# power.net
KiCad netlist of a schematic drawn in Altium Designer
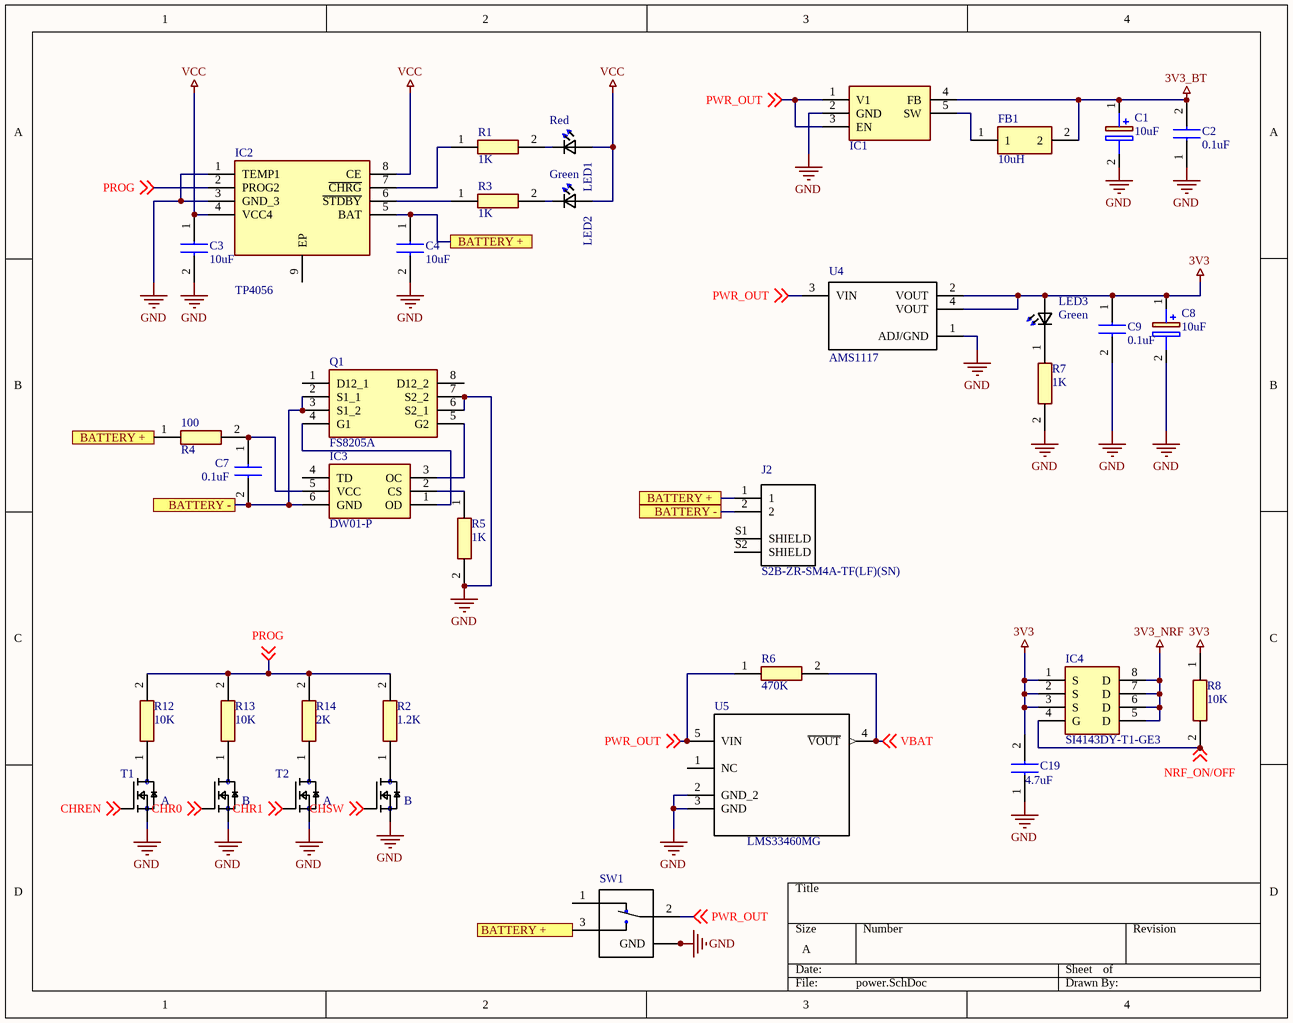
[diagram p0: power.SchDoc]

(export (version "E")
  (design (tool "Eeschema 10.0.6"))
  (components
    (comp (ref "C1")
      (value "10uF")
      (footprint "CAPPM3216X180N")
      (description "Capacitor Polarised")
      (fields (field (name "Comment") "tantalum capacitor 1206"))
      (libsource (lib "Radio Lib") (part "tantalum capacitor 1206"))
    )
    (comp (ref "C2")
      (value "0.1uF")
      (footprint "*CAPC1608X95N")
      (description "Capacitor")
      (fields (field (name "Comment") "capacitor 0603"))
      (libsource (lib "Radio Lib") (part "capacitor 0603"))
    )
    (comp (ref "C3")
      (value "10uF")
      (footprint "CAPC2012X94N")
      (description "Capacitor")
      (fields
        (field (name "MANUFACTURER_PART_NUMBER") "08055A101JAT2A")
        (field (name "MOUSER PART NUMBER") "581-08055A101J")
      )
      (libsource (lib "Radio Lib") (part "08055A101JAT2A"))
    )
    (comp (ref "C4")
      (value "10uF")
      (footprint "CAPC2012X94N")
      (description "Capacitor")
      (fields
        (field (name "MANUFACTURER_PART_NUMBER") "08055A101JAT2A")
        (field (name "MOUSER PART NUMBER") "581-08055A101J")
      )
      (libsource (lib "Radio Lib") (part "08055A101JAT2A"))
    )
    (comp (ref "C7")
      (value "0.1uF")
      (footprint "CAPC2012X94N")
      (description "Capacitor")
      (fields
        (field (name "MANUFACTURER_PART_NUMBER") "08055A101JAT2A")
        (field (name "MOUSER PART NUMBER") "581-08055A101J")
      )
      (libsource (lib "Radio Lib") (part "08055A101JAT2A"))
    )
    (comp (ref "C8")
      (value "10uF")
      (footprint "CAPPM3216X180N")
      (description "Capacitor Polarised")
      (fields (field (name "Comment") "tantalum capacitor 1206"))
      (libsource (lib "Radio Lib") (part "tantalum capacitor 1206"))
    )
    (comp (ref "C9")
      (value "0.1uF")
      (footprint "*CAPC1608X95N")
      (description "Capacitor")
      (fields (field (name "Comment") "capacitor 0603"))
      (libsource (lib "Radio Lib") (part "capacitor 0603"))
    )
    (comp (ref "C19")
      (value "4.7uF")
      (footprint "CAPC2012X94N")
      (description "Capacitor")
      (fields
        (field (name "MANUFACTURER_PART_NUMBER") "08055A101JAT2A")
        (field (name "MOUSER PART NUMBER") "581-08055A101J")
      )
      (libsource (lib "micromouse library") (part "08055A101JAT2A"))
    )
    (comp (ref "FB1")
      (value "10uH")
      (footprint "BEADC1608X95N")
      (description "Ferrite Bead")
      (fields (field (name "Comment") "inductor 0603"))
      (libsource (lib "Radio Lib") (part "inductor 0603"))
    )
    (comp (ref "IC1")
      (value "TPS62203")
      (footprint "SOT95P280X145-5N")
      (description "Integrated Circuit")
      (libsource (lib "Radio Lib") (part "TPS62203"))
    )
    (comp (ref "IC2")
      (value "TP4056")
      (footprint "SOIC127P600X175-9N")
      (description "Integrated Circuit")
      (libsource (lib "Radio Lib") (part "TP4056"))
    )
    (comp (ref "IC3")
      (value "DW01-P")
      (footprint "micromouse pcb library:SOT95P280X135-6N")
      (description "Integrated Circuit")
      (libsource (lib "Radio Lib") (part "DW01-P"))
    )
    (comp (ref "IC4")
      (value "SI4143DY-T1-GE3")
      (footprint "SI4143DY-T1-GE3")
      (description "Integrated Circuit")
      (libsource (lib "Radio Lib") (part "SI4143DY-T1-GE3"))
    )
    (comp (ref "J2")
      (value "S2B-ZR-SM4A-TF(LF)(SN)")
      (footprint "*JST_S2B-ZR-SM4A-TF(LF)(SN)_S2B-ZR-SM4A-TF(LF)(SN)(Primary)")
      (description "Connector Header Surface Mount, Right Angle 2 position 0.059 _1.50mm_")
      (fields (field (name "MF") "JST Sales") (field (name "MP") "S2B-ZR-SM4A-TF_LF__SN_"))
      (libsource (lib "Radio Lib") (part "S2B-ZR-SM4A-TF(LF)(SN)"))
    )
    (comp (ref "LED1")
      (value "Red")
      (footprint "*0603")
      (description "LED Indication - Discrete 3.4V 0603 _1608 Metric_")
      (fields (field (name "MP") "HSMR-C191") (field (name "MF") "Broadcom Limited"))
      (libsource (lib "Radio Lib") (part "HSMR-C191"))
    )
    (comp (ref "LED2")
      (value "Green")
      (footprint "*0603")
      (description "LED Indication - Discrete 3.4V 0603 _1608 Metric_")
      (fields (field (name "MP") "HSMR-C191") (field (name "MF") "Broadcom Limited"))
      (libsource (lib "Radio Lib") (part "HSMR-C191"))
    )
    (comp (ref "LED3")
      (value "Green")
      (footprint "*0603")
      (description "LED Indication - Discrete 3.4V 0603 _1608 Metric_")
      (fields (field (name "MP") "HSMR-C191") (field (name "MF") "Broadcom Limited"))
      (libsource (lib "Radio Lib") (part "HSMR-C191"))
    )
    (comp (ref "Q1")
      (value "FS8205A")
      (footprint "SOP65P640X120-8N")
      (description "Transistor")
      (libsource (lib "Radio Lib") (part "FS8205A"))
    )
    (comp (ref "R1")
      (value "1K")
      (footprint "RESC1608X55N")
      (description "Resistor")
      (fields (field (name "Comment") "resistor"))
      (libsource (lib "") (part "resistor_2"))
    )
    (comp (ref "R2")
      (value "1.2K")
      (footprint "RESC1608X55N")
      (description "Resistor")
      (fields (field (name "Comment") "resistor"))
      (libsource (lib "") (part "resistor_1"))
    )
    (comp (ref "R3")
      (value "1K")
      (footprint "RESC1608X55N")
      (description "Resistor")
      (fields (field (name "Comment") "resistor"))
      (libsource (lib "") (part "resistor_2"))
    )
    (comp (ref "R4")
      (value "100")
      (footprint "RESC2012X65N")
      (description "Resistor")
      (fields
        (field (name "MANUFACTURER_PART_NUMBER") "CPF0805B100KE")
        (field (name "MOUSER PART NUMBER") "279-CPF0805B100KE")
      )
      (libsource (lib "") (part "CPF0805_1"))
    )
    (comp (ref "R5")
      (value "1K")
      (footprint "RESC2012X65N")
      (description "Resistor")
      (fields
        (field (name "MANUFACTURER_PART_NUMBER") "CPF0805B100KE")
        (field (name "MOUSER PART NUMBER") "279-CPF0805B100KE")
      )
      (libsource (lib "Radio Lib") (part "CPF0805"))
    )
    (comp (ref "R6")
      (value "470K")
      (footprint "RESC1608X55N")
      (description "Resistor")
      (fields (field (name "Comment") "resistor"))
      (libsource (lib "") (part "resistor_2"))
    )
    (comp (ref "R7")
      (value "1K")
      (footprint "RESC1608X55N")
      (description "Resistor")
      (fields (field (name "Comment") "resistor"))
      (libsource (lib "Radio Lib") (part "resistor"))
    )
    (comp (ref "R8")
      (value "10K")
      (footprint "RESC2012X65N")
      (description "Resistor")
      (fields
        (field (name "MANUFACTURER_PART_NUMBER") "CPF0805B100KE")
        (field (name "MOUSER PART NUMBER") "279-CPF0805B100KE")
      )
      (libsource (lib "Radio Lib") (part "CPF0805"))
    )
    (comp (ref "R12")
      (value "10K")
      (footprint "RESC1608X55N")
      (description "Resistor")
      (fields (field (name "Comment") "resistor"))
      (libsource (lib "") (part "resistor_1"))
    )
    (comp (ref "R13")
      (value "10K")
      (footprint "RESC1608X55N")
      (description "Resistor")
      (fields (field (name "Comment") "resistor"))
      (libsource (lib "") (part "resistor_1"))
    )
    (comp (ref "R14")
      (value "2K")
      (footprint "RESC1608X55N")
      (description "Resistor")
      (fields (field (name "Comment") "resistor"))
      (libsource (lib "") (part "resistor_1"))
    )
    (comp (ref "SW1")
      (value "1437575-1")
      (footprint "*SW_MLL1200S_MLL1200S(Primary)")
      (description "Slide Switch SPDT Surface Mount, Right Angle")
      (fields (field (name "MP") "MLL1200S") (field (name "MF") "TE Connectivity"))
      (libsource (lib "Radio Lib") (part "MLL1200S"))
    )
    (comp (ref "T1")
      (value "PMGD780SN")
      (footprint "*SOP65P210X110-6N")
      (description "Mosfet Array 2 N-Channel _Dual_ 20V 1.2A 390mW Surface Mount 6-TSSOP")
      (fields (field (name "MF") "NXP Semiconductors"))
      (libsource (lib "Radio Lib") (part "PMGD780SN"))
    )
    (comp (ref "T2")
      (value "PMGD780SN")
      (footprint "*SOP65P210X110-6N")
      (description "Mosfet Array 2 N-Channel _Dual_ 20V 1.2A 390mW Surface Mount 6-TSSOP")
      (fields (field (name "MF") "NXP Semiconductors"))
      (libsource (lib "Radio Lib") (part "PMGD780SN"))
    )
    (comp (ref "U4")
      (value "AMS1117")
      (footprint "*SOT229P700X180-4N")
      (description "1A LOW DROPOUT VOLTAGE REGULATOR")
      (fields (field (name "MF") "Seeed Technology"))
      (libsource (lib "Radio Lib") (part "AMS1117"))
    )
    (comp (ref "U5")
      (value "LMS33460MG")
      (footprint "*SOT65P210X110-5N")
      (description "3V Under Voltage Detector 5-SC70 -40 to 85")
      (fields (field (name "MF") "Texas Instruments") (field (name "MP") "LMS33460MG/NOPB"))
      (libsource (lib "Radio Lib") (part "LMS33460MG"))
    )
  )
  (nets
    (net (code "1") (name "/BATTERY +") (class "Default")
      (node (ref "C4") (pin "1") (pinfunction "1_1") (pintype "passive"))
      (node (ref "IC2") (pin "5") (pinfunction "BAT_5") (pintype "passive"))
      (node (ref "J2") (pin "1") (pinfunction "1_1") (pintype "passive"))
      (node (ref "R4") (pin "1") (pinfunction "1_1") (pintype "passive"))
      (node (ref "SW1") (pin "3") (pinfunction "3_3") (pintype "passive"))
    )
    (net (code "2") (name "/BATTERY -") (class "Default")
      (node (ref "C7") (pin "2") (pinfunction "2_2") (pintype "passive"))
      (node (ref "IC3") (pin "6") (pinfunction "GND_6") (pintype "passive"))
      (node (ref "J2") (pin "2") (pinfunction "2_2") (pintype "passive"))
      (node (ref "Q1") (pin "2") (pinfunction "S1_1_2") (pintype "passive"))
      (node (ref "Q1") (pin "3") (pinfunction "S1_2_3") (pintype "passive"))
    )
    (net (code "3") (name "3V3") (class "Default")
      (node (ref "C19") (pin "2") (pinfunction "2_2") (pintype "passive"))
      (node (ref "C8") (pin "1") (pinfunction "+_1") (pintype "passive"))
      (node (ref "C9") (pin "1") (pinfunction "1_1") (pintype "passive"))
      (node (ref "IC4") (pin "1") (pinfunction "S_1") (pintype "passive"))
      (node (ref "IC4") (pin "2") (pinfunction "S_2") (pintype "passive"))
      (node (ref "IC4") (pin "3") (pinfunction "S_3") (pintype "passive"))
      (node (ref "LED3") (pin "2") (pinfunction "A2_2") (pintype "passive"))
      (node (ref "R8") (pin "1") (pinfunction "1_1") (pintype "passive"))
      (node (ref "U4") (pin "2") (pinfunction "VOUT_2") (pintype "power_in"))
      (node (ref "U4") (pin "4") (pinfunction "VOUT_4") (pintype "power_in"))
    )
    (net (code "4") (name "3V3_BT") (class "Default")
      (node (ref "C1") (pin "1") (pinfunction "+_1") (pintype "passive"))
      (node (ref "C2") (pin "2") (pinfunction "2_2") (pintype "passive"))
      (node (ref "FB1") (pin "2") (pinfunction "2_2") (pintype "passive"))
      (node (ref "IC1") (pin "4") (pinfunction "FB_4") (pintype "passive"))
    )
    (net (code "5") (name "3V3_NRF") (class "Default")
      (node (ref "IC4") (pin "5") (pinfunction "D_5") (pintype "passive"))
      (node (ref "IC4") (pin "6") (pinfunction "D_6") (pintype "passive"))
      (node (ref "IC4") (pin "7") (pinfunction "D_7") (pintype "passive"))
      (node (ref "IC4") (pin "8") (pinfunction "D_8") (pintype "power_in"))
    )
    (net (code "6") (name "CHR0") (class "Default")
      (node (ref "T1") (pin "5") (pinfunction "G_5") (pintype "passive"))
    )
    (net (code "7") (name "CHR1") (class "Default")
      (node (ref "T2") (pin "2") (pinfunction "G_2") (pintype "passive"))
    )
    (net (code "8") (name "CHREN") (class "Default")
      (node (ref "T1") (pin "2") (pinfunction "G_2") (pintype "passive"))
    )
    (net (code "9") (name "CHSW") (class "Default")
      (node (ref "T2") (pin "5") (pinfunction "G_5") (pintype "passive"))
    )
    (net (code "10") (name "GND") (class "Default")
      (node (ref "C1") (pin "2") (pinfunction "-_2") (pintype "passive"))
      (node (ref "C19") (pin "1") (pinfunction "1_1") (pintype "passive"))
      (node (ref "C2") (pin "1") (pinfunction "1_1") (pintype "passive"))
      (node (ref "C3") (pin "2") (pinfunction "2_2") (pintype "passive"))
      (node (ref "C4") (pin "2") (pinfunction "2_2") (pintype "passive"))
      (node (ref "C8") (pin "2") (pinfunction "-_2") (pintype "passive"))
      (node (ref "C9") (pin "2") (pinfunction "2_2") (pintype "passive"))
      (node (ref "IC1") (pin "2") (pinfunction "GND_2") (pintype "passive"))
      (node (ref "IC2") (pin "1") (pinfunction "TEMP1_1") (pintype "passive"))
      (node (ref "IC2") (pin "3") (pinfunction "GND_3_3") (pintype "passive"))
      (node (ref "Q1") (pin "6") (pinfunction "S2_1_6") (pintype "passive"))
      (node (ref "Q1") (pin "7") (pinfunction "S2_2_7") (pintype "passive"))
      (node (ref "R5") (pin "2") (pinfunction "2_2") (pintype "passive"))
      (node (ref "R7") (pin "2") (pinfunction "2_2") (pintype "passive"))
      (node (ref "SW1") (pin "G1") (pinfunction "GND_G1") (pintype "power_in"))
      (node (ref "SW1") (pin "G2") (pinfunction "GND_G2") (pintype "power_in"))
      (node (ref "SW1") (pin "G3") (pinfunction "GND_G3") (pintype "power_in"))
      (node (ref "SW1") (pin "G4") (pinfunction "GND_G4") (pintype "power_in"))
      (node (ref "T1") (pin "1") (pinfunction "S_1") (pintype "passive"))
      (node (ref "T1") (pin "4") (pinfunction "S_4") (pintype "passive"))
      (node (ref "T2") (pin "1") (pinfunction "S_1") (pintype "passive"))
      (node (ref "T2") (pin "4") (pinfunction "S_4") (pintype "passive"))
      (node (ref "U4") (pin "1") (pinfunction "ADJ/GND_1") (pintype "power_in"))
      (node (ref "U5") (pin "2") (pinfunction "GND_2_2") (pintype "passive"))
      (node (ref "U5") (pin "3") (pinfunction "GND_3") (pintype "passive"))
    )
    (net (code "11") (name "NRF_ON{slash}OFF") (class "Default")
      (node (ref "IC4") (pin "4") (pinfunction "G_4") (pintype "passive"))
      (node (ref "R8") (pin "2") (pinfunction "2_2") (pintype "passive"))
    )
    (net (code "12") (name "Net-(IC1-SW)") (class "Default")
      (node (ref "FB1") (pin "1") (pinfunction "1_1") (pintype "passive"))
      (node (ref "IC1") (pin "5") (pinfunction "SW_5") (pintype "passive"))
    )
    (net (code "13") (name "Net-(IC2-~{CHRG})") (class "Default")
      (node (ref "IC2") (pin "7") (pinfunction "~{CHRG}_7") (pintype "passive"))
      (node (ref "R1") (pin "1") (pinfunction "1_1") (pintype "passive"))
    )
    (net (code "14") (name "Net-(IC2-~{STDBY})") (class "Default")
      (node (ref "IC2") (pin "6") (pinfunction "~{STDBY}_6") (pintype "passive"))
      (node (ref "R3") (pin "1") (pinfunction "1_1") (pintype "passive"))
    )
    (net (code "15") (name "Net-(IC3-CS)") (class "Default")
      (node (ref "IC3") (pin "2") (pinfunction "CS_2") (pintype "passive"))
      (node (ref "R5") (pin "1") (pinfunction "1_1") (pintype "passive"))
    )
    (net (code "16") (name "Net-(IC3-OC)") (class "Default")
      (node (ref "IC3") (pin "3") (pinfunction "OC_3") (pintype "passive"))
      (node (ref "Q1") (pin "5") (pinfunction "G2_5") (pintype "passive"))
    )
    (net (code "17") (name "Net-(IC3-OD)") (class "Default")
      (node (ref "IC3") (pin "1") (pinfunction "OD_1") (pintype "passive"))
      (node (ref "Q1") (pin "4") (pinfunction "G1_4") (pintype "passive"))
    )
    (net (code "18") (name "Net-(IC3-VCC)") (class "Default")
      (node (ref "C7") (pin "1") (pinfunction "1_1") (pintype "passive"))
      (node (ref "IC3") (pin "5") (pinfunction "VCC_5") (pintype "passive"))
      (node (ref "R4") (pin "2") (pinfunction "2_2") (pintype "passive"))
    )
    (net (code "19") (name "Net-(LED1-K2)") (class "Default")
      (node (ref "LED1") (pin "1") (pinfunction "K2_1") (pintype "passive"))
      (node (ref "R1") (pin "2") (pinfunction "2_2") (pintype "passive"))
    )
    (net (code "20") (name "Net-(LED2-K2)") (class "Default")
      (node (ref "LED2") (pin "1") (pinfunction "K2_1") (pintype "passive"))
      (node (ref "R3") (pin "2") (pinfunction "2_2") (pintype "passive"))
    )
    (net (code "21") (name "Net-(LED3-K2)") (class "Default")
      (node (ref "LED3") (pin "1") (pinfunction "K2_1") (pintype "passive"))
      (node (ref "R7") (pin "1") (pinfunction "1_1") (pintype "passive"))
    )
    (net (code "22") (name "Net-(R2-Pad1)") (class "Default")
      (node (ref "R2") (pin "1") (pinfunction "1_1") (pintype "passive"))
      (node (ref "T2") (pin "3") (pinfunction "D_3") (pintype "passive"))
    )
    (net (code "23") (name "Net-(R12-Pad1)") (class "Default")
      (node (ref "R12") (pin "1") (pinfunction "1_1") (pintype "passive"))
      (node (ref "T1") (pin "6") (pinfunction "D_6") (pintype "passive"))
    )
    (net (code "24") (name "Net-(R13-Pad1)") (class "Default")
      (node (ref "R13") (pin "1") (pinfunction "1_1") (pintype "passive"))
      (node (ref "T1") (pin "3") (pinfunction "D_3") (pintype "passive"))
    )
    (net (code "25") (name "Net-(R14-Pad1)") (class "Default")
      (node (ref "R14") (pin "1") (pinfunction "1_1") (pintype "passive"))
      (node (ref "T2") (pin "6") (pinfunction "D_6") (pintype "passive"))
    )
    (net (code "26") (name "PROG") (class "Default")
      (node (ref "IC2") (pin "2") (pinfunction "PROG2_2") (pintype "passive"))
      (node (ref "R12") (pin "2") (pinfunction "2_2") (pintype "passive"))
      (node (ref "R13") (pin "2") (pinfunction "2_2") (pintype "passive"))
      (node (ref "R14") (pin "2") (pinfunction "2_2") (pintype "passive"))
      (node (ref "R2") (pin "2") (pinfunction "2_2") (pintype "passive"))
    )
    (net (code "27") (name "PWR_OUT") (class "Default")
      (node (ref "IC1") (pin "1") (pinfunction "V1_1") (pintype "passive"))
      (node (ref "IC1") (pin "3") (pinfunction "EN_3") (pintype "passive"))
      (node (ref "R6") (pin "1") (pinfunction "1_1") (pintype "passive"))
      (node (ref "SW1") (pin "2") (pinfunction "2_2") (pintype "passive"))
      (node (ref "U4") (pin "3") (pinfunction "VIN_3") (pintype "power_in"))
      (node (ref "U5") (pin "5") (pinfunction "VIN_5") (pintype "power_in"))
    )
    (net (code "28") (name "VBAT") (class "Default")
      (node (ref "R6") (pin "2") (pinfunction "2_2") (pintype "passive"))
      (node (ref "U5") (pin "4") (pinfunction "~{VOUT}_4") (pintype "output"))
    )
    (net (code "29") (name "VCC") (class "Default")
      (node (ref "C3") (pin "1") (pinfunction "1_1") (pintype "passive"))
      (node (ref "IC2") (pin "4") (pinfunction "VCC4_4") (pintype "passive"))
      (node (ref "IC2") (pin "8") (pinfunction "CE_8") (pintype "passive"))
      (node (ref "LED1") (pin "2") (pinfunction "A2_2") (pintype "passive"))
      (node (ref "LED2") (pin "2") (pinfunction "A2_2") (pintype "passive"))
    )
    (net (code "30") (name "unconnected-(IC2-EP-Pad9)") (class "Default")
      (node (ref "IC2") (pin "9") (pinfunction "EP_9") (pintype "passive"))
    )
    (net (code "31") (name "unconnected-(IC3-TD-Pad4)") (class "Default")
      (node (ref "IC3") (pin "4") (pinfunction "TD_4") (pintype "passive"))
    )
    (net (code "32") (name "unconnected-(J2-SHIELD-PadS1)") (class "Default")
      (node (ref "J2") (pin "S1") (pinfunction "SHIELD_S1") (pintype "passive"))
    )
    (net (code "33") (name "unconnected-(J2-SHIELD-PadS2)") (class "Default")
      (node (ref "J2") (pin "S2") (pinfunction "SHIELD_S2") (pintype "passive"))
    )
    (net (code "34") (name "unconnected-(Q1-D12_1-Pad1)") (class "Default")
      (node (ref "Q1") (pin "1") (pinfunction "D12_1_1") (pintype "passive"))
    )
    (net (code "35") (name "unconnected-(Q1-D12_2-Pad8)") (class "Default")
      (node (ref "Q1") (pin "8") (pinfunction "D12_2_8") (pintype "passive"))
    )
    (net (code "36") (name "unconnected-(SW1-Pad1)") (class "Default")
      (node (ref "SW1") (pin "1") (pinfunction "1_1") (pintype "passive"))
    )
    (net (code "37") (name "unconnected-(U5-NC-Pad1)") (class "Default")
      (node (ref "U5") (pin "1") (pinfunction "NC_1") (pintype "passive"))
    )
  )
)
